# VGA_6bits.net
KiCad netlist of a schematic drawn in Altium Designer
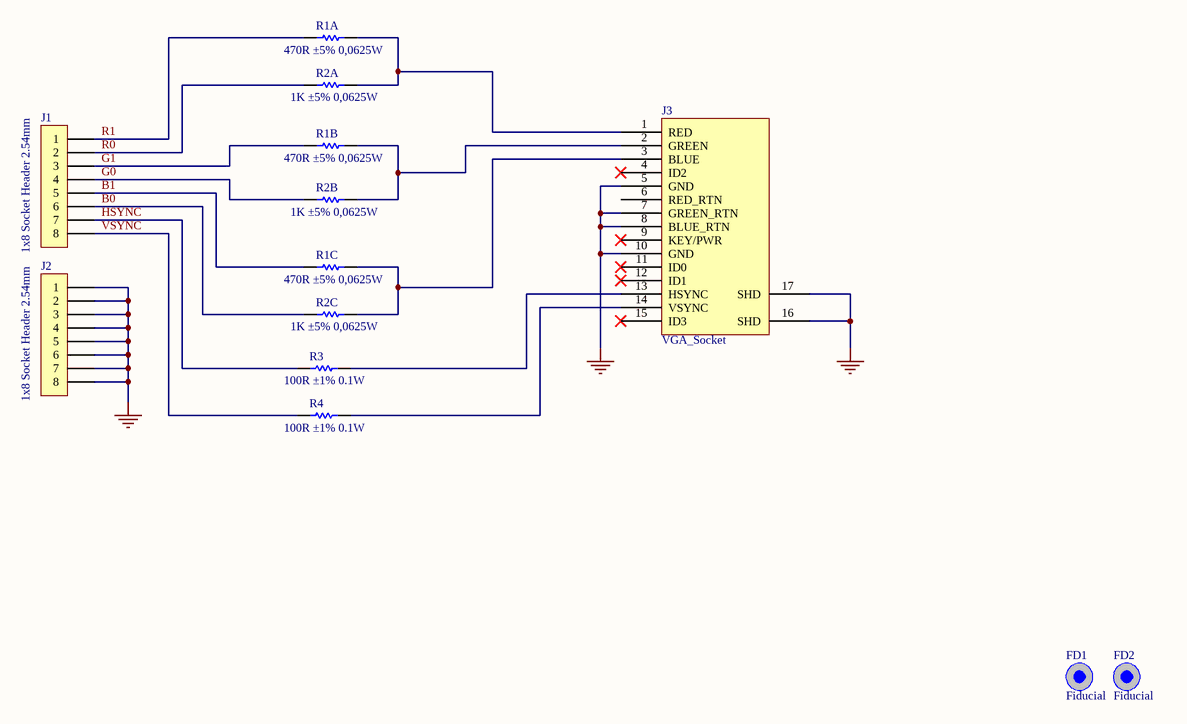
[diagram p0: VGA_6bits.SchDoc]

(export (version "E")
  (design (tool "Eeschema 10.0.6"))
  (components
    (comp (ref "FD1")
      (value "Fiducial")
      (footprint "Fiducial_1mm")
      (description "Fiducial Mark")
      (fields (field (name "PART NUMBER") "Fiducial 1mm"))
      (libsource (lib "Miscelanea") (part "Fiducial"))
    )
    (comp (ref "FD2")
      (value "Fiducial")
      (footprint "Fiducial_1mm")
      (description "Fiducial Mark")
      (fields (field (name "PART NUMBER") "Fiducial 1mm"))
      (libsource (lib "Miscelanea") (part "Fiducial"))
    )
    (comp (ref "J1")
      (value "1x8 Socket Header 2.54mm")
      (footprint "1x8 Socket Header THT 2.54mm")
      (description "Connector, 8 pin Socket Header 2.54mm")
      (fields (field (name "MANUFACTURER") "Samtec") (field (name "PART NUMBER") "CON_SH_THT2.54_8"))
      (libsource (lib "Connector_SocketHeader_2.54") (part "1x8 Socket Header 2.54mm"))
    )
    (comp (ref "J2")
      (value "1x8 Socket Header 2.54mm")
      (footprint "1x8 Socket Header THT 2.54mm")
      (description "Connector, 8 pin Socket Header 2.54mm")
      (fields (field (name "MANUFACTURER") "Samtec") (field (name "PART NUMBER") "CON_SH_THT2.54_8"))
      (libsource (lib "Connector_SocketHeader_2.54") (part "1x8 Socket Header 2.54mm"))
    )
    (comp (ref "J3")
      (value "VGA_Socket")
      (footprint "VGA_RA_SLIM")
      (fields (field (name "PART NUMBER") "VGA_RA_SLIM"))
      (libsource (lib "Connectors_AV") (part "VGA_Socket"))
    )
    (comp (ref "R1")
      (value "470R ±5% 0,0625W")
      (footprint "4xArray_1206_Convex")
      (description "Resistor")
      (fields
        (field (name "PART NUMBER") "4xArray_1206_Convex_470R_0,0625W_±5%")
        (field (name "POWER") "0,0625W")
      )
      (libsource (lib "Pasives_Resistor_SMD") (part "Resistor_x4_Parts"))
    )
    (comp (ref "R2")
      (value "1K ±5% 0,0625W")
      (footprint "4xArray_1206_Convex")
      (description "Resistor")
      (fields
        (field (name "PART NUMBER") "4xArray_1206_Convex_1K_0,0625W_±5%")
        (field (name "POWER") "0,0625W")
      )
      (libsource (lib "Pasives_Resistor_SMD") (part "Resistor_x4_Parts"))
    )
    (comp (ref "R3")
      (value "100R ±1% 0.1W")
      (footprint "R0603")
      (description "Resistor, SMD")
      (fields (field (name "TOLERANCE") "±1%") (field (name "POWER") "0.1W"))
      (libsource (lib "Pasives_Resistor_SMD") (part "Resistor"))
    )
    (comp (ref "R4")
      (value "100R ±1% 0.1W")
      (footprint "R0603")
      (description "Resistor, SMD")
      (fields (field (name "TOLERANCE") "±1%") (field (name "POWER") "0.1W"))
      (libsource (lib "Pasives_Resistor_SMD") (part "Resistor"))
    )
  )
  (nets
    (net (code "1") (name "/B0") (class "Default")
      (node (ref "J1") (pin "6") (pinfunction "6_6") (pintype "passive"))
      (node (ref "R2") (pin "3") (pinfunction "3_3") (pintype "passive"))
    )
    (net (code "2") (name "/B1") (class "Default")
      (node (ref "J1") (pin "5") (pinfunction "5_5") (pintype "passive"))
      (node (ref "R1") (pin "3") (pinfunction "3_3") (pintype "passive"))
    )
    (net (code "3") (name "/G0") (class "Default")
      (node (ref "J1") (pin "4") (pinfunction "4_4") (pintype "passive"))
      (node (ref "R2") (pin "2") (pinfunction "2_2") (pintype "passive"))
    )
    (net (code "4") (name "/G1") (class "Default")
      (node (ref "J1") (pin "3") (pinfunction "3_3") (pintype "passive"))
      (node (ref "R1") (pin "2") (pinfunction "2_2") (pintype "passive"))
    )
    (net (code "5") (name "/HSYNC") (class "Default")
      (node (ref "J1") (pin "7") (pinfunction "7_7") (pintype "passive"))
      (node (ref "R3") (pin "1") (pinfunction "1_1") (pintype "passive"))
    )
    (net (code "6") (name "/R0") (class "Default")
      (node (ref "J1") (pin "2") (pinfunction "2_2") (pintype "passive"))
      (node (ref "R2") (pin "1") (pinfunction "1_1") (pintype "passive"))
    )
    (net (code "7") (name "/R1") (class "Default")
      (node (ref "J1") (pin "1") (pinfunction "1_1") (pintype "passive"))
      (node (ref "R1") (pin "1") (pinfunction "1_1") (pintype "passive"))
    )
    (net (code "8") (name "/VSYNC") (class "Default")
      (node (ref "J1") (pin "8") (pinfunction "8_8") (pintype "passive"))
      (node (ref "R4") (pin "1") (pinfunction "1_1") (pintype "passive"))
    )
    (net (code "9") (name "GND") (class "Default")
      (node (ref "J2") (pin "1") (pinfunction "1_1") (pintype "passive"))
      (node (ref "J2") (pin "2") (pinfunction "2_2") (pintype "passive"))
      (node (ref "J2") (pin "3") (pinfunction "3_3") (pintype "passive"))
      (node (ref "J2") (pin "4") (pinfunction "4_4") (pintype "passive"))
      (node (ref "J2") (pin "5") (pinfunction "5_5") (pintype "passive"))
      (node (ref "J2") (pin "6") (pinfunction "6_6") (pintype "passive"))
      (node (ref "J2") (pin "7") (pinfunction "7_7") (pintype "passive"))
      (node (ref "J2") (pin "8") (pinfunction "8_8") (pintype "passive"))
      (node (ref "J3") (pin "10") (pinfunction "GND_10") (pintype "passive"))
      (node (ref "J3") (pin "16") (pinfunction "SHD_16") (pintype "passive"))
      (node (ref "J3") (pin "17") (pinfunction "SHD_17") (pintype "passive"))
      (node (ref "J3") (pin "5") (pinfunction "GND_5") (pintype "passive"))
      (node (ref "J3") (pin "7") (pinfunction "GREEN_RTN_7") (pintype "passive"))
      (node (ref "J3") (pin "8") (pinfunction "BLUE_RTN_8") (pintype "passive"))
    )
    (net (code "10") (name "Net-(J3-BLUE)") (class "Default")
      (node (ref "J3") (pin "3") (pinfunction "BLUE_3") (pintype "passive"))
      (node (ref "R1") (pin "6") (pinfunction "6_6") (pintype "passive"))
      (node (ref "R2") (pin "6") (pinfunction "6_6") (pintype "passive"))
    )
    (net (code "11") (name "Net-(J3-GREEN)") (class "Default")
      (node (ref "J3") (pin "2") (pinfunction "GREEN_2") (pintype "passive"))
      (node (ref "R1") (pin "7") (pinfunction "7_7") (pintype "passive"))
      (node (ref "R2") (pin "7") (pinfunction "7_7") (pintype "passive"))
    )
    (net (code "12") (name "Net-(J3-HSYNC)") (class "Default")
      (node (ref "J3") (pin "13") (pinfunction "HSYNC_13") (pintype "passive"))
      (node (ref "R3") (pin "2") (pinfunction "2_2") (pintype "passive"))
    )
    (net (code "13") (name "Net-(J3-RED)") (class "Default")
      (node (ref "J3") (pin "1") (pinfunction "RED_1") (pintype "passive"))
      (node (ref "R1") (pin "8") (pinfunction "8_8") (pintype "passive"))
      (node (ref "R2") (pin "8") (pinfunction "8_8") (pintype "passive"))
    )
    (net (code "14") (name "Net-(J3-VSYNC)") (class "Default")
      (node (ref "J3") (pin "14") (pinfunction "VSYNC_14") (pintype "passive"))
      (node (ref "R4") (pin "2") (pinfunction "2_2") (pintype "passive"))
    )
    (net (code "15") (name "unconnected-(J3-ID0-Pad11)") (class "Default")
      (node (ref "J3") (pin "11") (pinfunction "ID0_11") (pintype "passive+no_connect"))
    )
    (net (code "16") (name "unconnected-(J3-ID1-Pad12)") (class "Default")
      (node (ref "J3") (pin "12") (pinfunction "ID1_12") (pintype "passive+no_connect"))
    )
    (net (code "17") (name "unconnected-(J3-ID2-Pad4)") (class "Default")
      (node (ref "J3") (pin "4") (pinfunction "ID2_4") (pintype "passive+no_connect"))
    )
    (net (code "18") (name "unconnected-(J3-ID3-Pad15)") (class "Default")
      (node (ref "J3") (pin "15") (pinfunction "ID3_15") (pintype "passive+no_connect"))
    )
    (net (code "19") (name "unconnected-(J3-KEY{slash}PWR-Pad9)") (class "Default")
      (node (ref "J3") (pin "9") (pinfunction "KEY/PWR_9") (pintype "passive+no_connect"))
    )
    (net (code "20") (name "unconnected-(J3-RED_RTN-Pad6)") (class "Default")
      (node (ref "J3") (pin "6") (pinfunction "RED_RTN_6") (pintype "passive"))
    )
  )
)
